# lighting.net
KiCad netlist of a schematic drawn in EAGLE
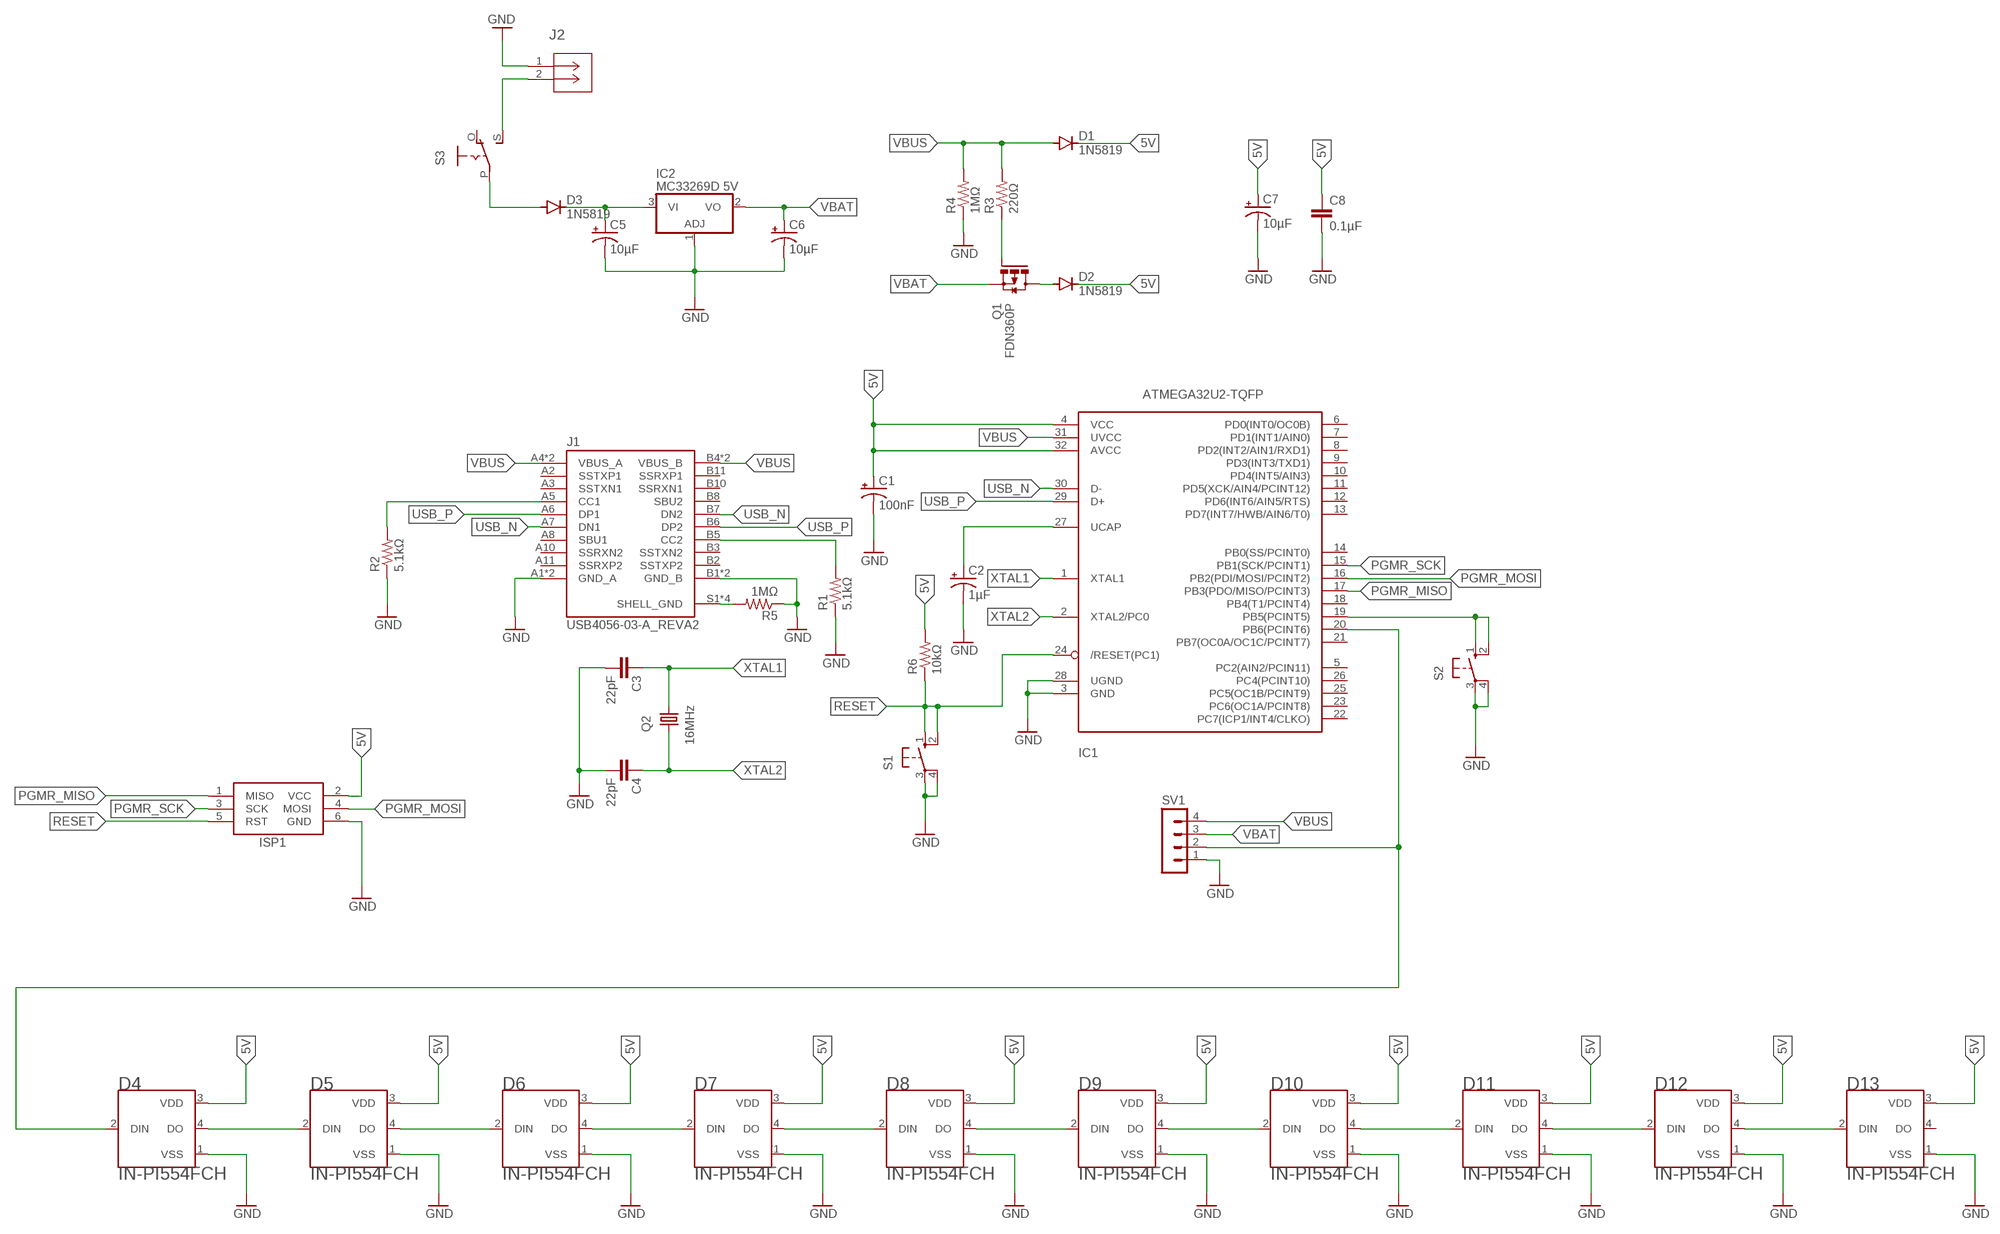
[diagram p0: schematic, sheet 1]

(export (version "E")
  (design (tool "Eeschema 10.0.6"))
  (components
    (comp (ref "C1")
      (value "100nF")
      (footprint "eagle-import:PANASONIC_B")
      (libsource (lib "eagle-import") (part "CPOL-USB"))
    )
    (comp (ref "C2")
      (value "1µF")
      (footprint "eagle-import:E2-5")
      (libsource (lib "eagle-import") (part "CPOL-USE2-5"))
    )
    (comp (ref "C3")
      (value "22pF")
      (footprint "eagle-import:C0402")
      (libsource (lib "eagle-import") (part "C-EUC0402"))
    )
    (comp (ref "C4")
      (value "22pF")
      (footprint "eagle-import:C0402")
      (libsource (lib "eagle-import") (part "C-EUC0402"))
    )
    (comp (ref "C5")
      (value "10µF")
      (footprint "eagle-import:PANASONIC_B")
      (libsource (lib "eagle-import") (part "CPOL-USB"))
    )
    (comp (ref "C6")
      (value "10µF")
      (footprint "eagle-import:PANASONIC_B")
      (libsource (lib "eagle-import") (part "CPOL-USB"))
    )
    (comp (ref "C7")
      (value "10µF")
      (footprint "eagle-import:PANASONIC_B")
      (libsource (lib "eagle-import") (part "CPOL-USB"))
    )
    (comp (ref "C8")
      (value "0.1µF")
      (footprint "eagle-import:C0402")
      (libsource (lib "eagle-import") (part "C-EUC0402"))
    )
    (comp (ref "D1")
      (value "1N5819")
      (footprint "eagle-import:DO15-12")
      (libsource (lib "eagle-import") (part "DIODE-DO15-12"))
    )
    (comp (ref "D2")
      (value "1N5819")
      (footprint "eagle-import:DO15-12")
      (libsource (lib "eagle-import") (part "DIODE-DO15-12"))
    )
    (comp (ref "D3")
      (value "1N5819")
      (footprint "eagle-import:DO15-12")
      (libsource (lib "eagle-import") (part "DIODE-DO15-12"))
    )
    (comp (ref "D4")
      (value "IN-PI554FCH")
      (footprint "eagle-import:LED_IN-PI554FCH")
      (fields (field (name "MANUFACTURER") "Inolux"))
      (libsource (lib "eagle-import") (part "IN-PI554FCH"))
    )
    (comp (ref "D5")
      (value "IN-PI554FCH")
      (footprint "eagle-import:LED_IN-PI554FCH")
      (fields (field (name "MANUFACTURER") "Inolux"))
      (libsource (lib "eagle-import") (part "IN-PI554FCH"))
    )
    (comp (ref "D6")
      (value "IN-PI554FCH")
      (footprint "eagle-import:LED_IN-PI554FCH")
      (fields (field (name "MANUFACTURER") "Inolux"))
      (libsource (lib "eagle-import") (part "IN-PI554FCH"))
    )
    (comp (ref "D7")
      (value "IN-PI554FCH")
      (footprint "eagle-import:LED_IN-PI554FCH")
      (fields (field (name "MANUFACTURER") "Inolux"))
      (libsource (lib "eagle-import") (part "IN-PI554FCH"))
    )
    (comp (ref "D8")
      (value "IN-PI554FCH")
      (footprint "eagle-import:LED_IN-PI554FCH")
      (fields (field (name "MANUFACTURER") "Inolux"))
      (libsource (lib "eagle-import") (part "IN-PI554FCH"))
    )
    (comp (ref "D9")
      (value "IN-PI554FCH")
      (footprint "eagle-import:LED_IN-PI554FCH")
      (fields (field (name "MANUFACTURER") "Inolux"))
      (libsource (lib "eagle-import") (part "IN-PI554FCH"))
    )
    (comp (ref "D10")
      (value "IN-PI554FCH")
      (footprint "eagle-import:LED_IN-PI554FCH")
      (fields (field (name "MANUFACTURER") "Inolux"))
      (libsource (lib "eagle-import") (part "IN-PI554FCH"))
    )
    (comp (ref "D11")
      (value "IN-PI554FCH")
      (footprint "eagle-import:LED_IN-PI554FCH")
      (fields (field (name "MANUFACTURER") "Inolux"))
      (libsource (lib "eagle-import") (part "IN-PI554FCH"))
    )
    (comp (ref "D12")
      (value "IN-PI554FCH")
      (footprint "eagle-import:LED_IN-PI554FCH")
      (fields (field (name "MANUFACTURER") "Inolux"))
      (libsource (lib "eagle-import") (part "IN-PI554FCH"))
    )
    (comp (ref "D13")
      (value "IN-PI554FCH")
      (footprint "eagle-import:LED_IN-PI554FCH")
      (fields (field (name "MANUFACTURER") "Inolux"))
      (libsource (lib "eagle-import") (part "IN-PI554FCH"))
    )
    (comp (ref "IC1")
      (value "ATMEGA32U2-TQFP")
      (footprint "eagle-import:TQFP32-08")
      (libsource (lib "eagle-import") (part "ATMEGA32U2-TQFP"))
    )
    (comp (ref "IC2")
      (value "MC33269D 5V")
      (footprint "eagle-import:DPACK")
      (libsource (lib "eagle-import") (part "MC33269?D"))
    )
    (comp (ref "ISP1")
      (value "AVRISP-BOX")
      (footprint "eagle-import:AVRISP-BOX")
      (libsource (lib "eagle-import") (part "AVRISP-BOX"))
    )
    (comp (ref "J1")
      (value "USB4056-03-A_REVA2")
      (footprint "eagle-import:GCT_USB4056-03-A_REVA2")
      (fields (field (name "MANUFACTURER") "GCT"))
      (libsource (lib "eagle-import") (part "USB4056-03-A_REVA2"))
    )
    (comp (ref "J2")
      (value "BH9VPC 9V")
      (footprint "eagle-import:CONN_BH9VPC_MPD")
      (fields
        (field (name "MANUFACTURER_PART_NUMBER") "BH9VPC")
        (field (name "COPYRIGHT") "Copyright (C) 2024 Ultra Librarian. All rights reserved.")
      )
      (libsource (lib "eagle-import") (part "BH9VPC"))
    )
    (comp (ref "Q1")
      (value "FDN360P")
      (footprint "eagle-import:SUPER-SOT3")
      (libsource (lib "eagle-import") (part "FDN360P"))
    )
    (comp (ref "Q2")
      (value "16MHz")
      (footprint "eagle-import:HC49U-V")
      (libsource (lib "eagle-import") (part "CRYSTALHC49U-V"))
    )
    (comp (ref "R1")
      (value "5.1kΩ")
      (footprint "eagle-import:0207_10")
      (libsource (lib "eagle-import") (part "R-US_0207/10"))
    )
    (comp (ref "R2")
      (value "5.1kΩ")
      (footprint "eagle-import:0207_10")
      (libsource (lib "eagle-import") (part "R-US_0207/10"))
    )
    (comp (ref "R3")
      (value "220Ω")
      (footprint "eagle-import:0207_10")
      (libsource (lib "eagle-import") (part "R-US_0207/10"))
    )
    (comp (ref "R4")
      (value "1MΩ")
      (footprint "eagle-import:0207_10")
      (libsource (lib "eagle-import") (part "R-US_0207/10"))
    )
    (comp (ref "R5")
      (value "1MΩ")
      (footprint "eagle-import:0207_10")
      (libsource (lib "eagle-import") (part "R-US_0207/10"))
    )
    (comp (ref "R6")
      (value "10kΩ")
      (footprint "eagle-import:0207_10")
      (libsource (lib "eagle-import") (part "R-US_0207/10"))
    )
    (comp (ref "S1")
      (value "10-XX")
      (footprint "eagle-import:B3F-10XX")
      (fields (field (name "MPN") "B3F-1000"))
      (libsource (lib "eagle-import") (part "10-XX"))
    )
    (comp (ref "S2")
      (value "10-XX")
      (footprint "eagle-import:B3F-10XX")
      (fields (field (name "MPN") "B3F-1000"))
      (libsource (lib "eagle-import") (part "10-XX"))
    )
    (comp (ref "S3")
      (value "EG1218S")
      (footprint "eagle-import:EG1218")
      (libsource (lib "eagle-import") (part "EG1218S"))
    )
    (comp (ref "SV1")
      (value "MA04-1")
      (footprint "eagle-import:MA04-1")
      (libsource (lib "eagle-import") (part "MA04-1"))
    )
  )
  (nets
    (net (code "1") (name "5V") (class "Default")
      (node (ref "C1") (pin "+") (pinfunction "+_+") (pintype "passive"))
      (node (ref "C7") (pin "+") (pinfunction "+_+") (pintype "passive"))
      (node (ref "C8") (pin "1") (pinfunction "1_1") (pintype "passive"))
      (node (ref "D1") (pin "C") (pinfunction "C_C") (pintype "passive"))
      (node (ref "D10") (pin "3") (pinfunction "VDD_3") (pintype "power_in"))
      (node (ref "D11") (pin "3") (pinfunction "VDD_3") (pintype "power_in"))
      (node (ref "D12") (pin "3") (pinfunction "VDD_3") (pintype "power_in"))
      (node (ref "D13") (pin "3") (pinfunction "VDD_3") (pintype "power_in"))
      (node (ref "D2") (pin "C") (pinfunction "C_C") (pintype "passive"))
      (node (ref "D4") (pin "3") (pinfunction "VDD_3") (pintype "power_in"))
      (node (ref "D5") (pin "3") (pinfunction "VDD_3") (pintype "power_in"))
      (node (ref "D6") (pin "3") (pinfunction "VDD_3") (pintype "power_in"))
      (node (ref "D7") (pin "3") (pinfunction "VDD_3") (pintype "power_in"))
      (node (ref "D8") (pin "3") (pinfunction "VDD_3") (pintype "power_in"))
      (node (ref "D9") (pin "3") (pinfunction "VDD_3") (pintype "power_in"))
      (node (ref "IC1") (pin "32") (pinfunction "AVCC_32") (pintype "bidirectional"))
      (node (ref "IC1") (pin "4") (pinfunction "VCC_4") (pintype "bidirectional"))
      (node (ref "ISP1") (pin "2") (pinfunction "VCC_2") (pintype "power_in"))
      (node (ref "R6") (pin "2") (pinfunction "2_2") (pintype "passive"))
    )
    (net (code "2") (name "GND") (class "Default")
      (node (ref "C1") (pin "-") (pinfunction "-_-") (pintype "passive"))
      (node (ref "C2") (pin "-") (pinfunction "-_-") (pintype "passive"))
      (node (ref "C3") (pin "2") (pinfunction "2_2") (pintype "passive"))
      (node (ref "C4") (pin "2") (pinfunction "2_2") (pintype "passive"))
      (node (ref "C5") (pin "-") (pinfunction "-_-") (pintype "passive"))
      (node (ref "C6") (pin "-") (pinfunction "-_-") (pintype "passive"))
      (node (ref "C7") (pin "-") (pinfunction "-_-") (pintype "passive"))
      (node (ref "C8") (pin "2") (pinfunction "2_2") (pintype "passive"))
      (node (ref "D10") (pin "1") (pinfunction "VSS_1") (pintype "power_in"))
      (node (ref "D11") (pin "1") (pinfunction "VSS_1") (pintype "power_in"))
      (node (ref "D12") (pin "1") (pinfunction "VSS_1") (pintype "power_in"))
      (node (ref "D13") (pin "1") (pinfunction "VSS_1") (pintype "power_in"))
      (node (ref "D4") (pin "1") (pinfunction "VSS_1") (pintype "power_in"))
      (node (ref "D5") (pin "1") (pinfunction "VSS_1") (pintype "power_in"))
      (node (ref "D6") (pin "1") (pinfunction "VSS_1") (pintype "power_in"))
      (node (ref "D7") (pin "1") (pinfunction "VSS_1") (pintype "power_in"))
      (node (ref "D8") (pin "1") (pinfunction "VSS_1") (pintype "power_in"))
      (node (ref "D9") (pin "1") (pinfunction "VSS_1") (pintype "power_in"))
      (node (ref "IC1") (pin "28") (pinfunction "UGND_28") (pintype "bidirectional"))
      (node (ref "IC1") (pin "3") (pinfunction "GND_3") (pintype "bidirectional"))
      (node (ref "IC2") (pin "1") (pinfunction "ADJ_1") (pintype "input"))
      (node (ref "ISP1") (pin "6") (pinfunction "GND_6") (pintype "power_in"))
      (node (ref "J1") (pin "A1") (pinfunction "GND_A_A1") (pintype "power_in"))
      (node (ref "J1") (pin "A12") (pinfunction "GND_A_A12") (pintype "power_in"))
      (node (ref "J1") (pin "B1") (pinfunction "GND_B_B1") (pintype "power_in"))
      (node (ref "J1") (pin "B12") (pinfunction "GND_B_B12") (pintype "power_in"))
      (node (ref "J2") (pin "1") (pinfunction "1_1") (pintype "passive"))
      (node (ref "R1") (pin "1") (pinfunction "1_1") (pintype "passive"))
      (node (ref "R2") (pin "1") (pinfunction "1_1") (pintype "passive"))
      (node (ref "R4") (pin "1") (pinfunction "1_1") (pintype "passive"))
      (node (ref "R5") (pin "1") (pinfunction "1_1") (pintype "passive"))
      (node (ref "S1") (pin "3") (pinfunction "P_3") (pintype "passive"))
      (node (ref "S1") (pin "4") (pinfunction "P1_4") (pintype "passive"))
      (node (ref "S2") (pin "3") (pinfunction "P_3") (pintype "passive"))
      (node (ref "S2") (pin "4") (pinfunction "P1_4") (pintype "passive"))
      (node (ref "SV1") (pin "1") (pinfunction "1_1") (pintype "passive"))
    )
    (net (code "3") (name "Net-(D3-PadA)") (class "Default")
      (node (ref "D3") (pin "A") (pinfunction "A_A") (pintype "passive"))
      (node (ref "S3") (pin "P") (pinfunction "P_P") (pintype "passive"))
    )
    (net (code "4") (name "Net-(D4-DIN)") (class "Default")
      (node (ref "D4") (pin "2") (pinfunction "DIN_2") (pintype "input"))
      (node (ref "IC1") (pin "20") (pinfunction "PB6(PCINT6)_20") (pintype "bidirectional"))
      (node (ref "SV1") (pin "2") (pinfunction "2_2") (pintype "passive"))
    )
    (net (code "5") (name "Net-(D4-DO)") (class "Default")
      (node (ref "D4") (pin "4") (pinfunction "DO_4") (pintype "output"))
      (node (ref "D5") (pin "2") (pinfunction "DIN_2") (pintype "input"))
    )
    (net (code "6") (name "Net-(D5-DO)") (class "Default")
      (node (ref "D5") (pin "4") (pinfunction "DO_4") (pintype "output"))
      (node (ref "D6") (pin "2") (pinfunction "DIN_2") (pintype "input"))
    )
    (net (code "7") (name "Net-(D6-DO)") (class "Default")
      (node (ref "D6") (pin "4") (pinfunction "DO_4") (pintype "output"))
      (node (ref "D7") (pin "2") (pinfunction "DIN_2") (pintype "input"))
    )
    (net (code "8") (name "Net-(D7-DO)") (class "Default")
      (node (ref "D7") (pin "4") (pinfunction "DO_4") (pintype "output"))
      (node (ref "D8") (pin "2") (pinfunction "DIN_2") (pintype "input"))
    )
    (net (code "9") (name "Net-(D8-DO)") (class "Default")
      (node (ref "D8") (pin "4") (pinfunction "DO_4") (pintype "output"))
      (node (ref "D9") (pin "2") (pinfunction "DIN_2") (pintype "input"))
    )
    (net (code "10") (name "Net-(D10-DIN)") (class "Default")
      (node (ref "D10") (pin "2") (pinfunction "DIN_2") (pintype "input"))
      (node (ref "D9") (pin "4") (pinfunction "DO_4") (pintype "output"))
    )
    (net (code "11") (name "Net-(D10-DO)") (class "Default")
      (node (ref "D10") (pin "4") (pinfunction "DO_4") (pintype "output"))
      (node (ref "D11") (pin "2") (pinfunction "DIN_2") (pintype "input"))
    )
    (net (code "12") (name "Net-(D11-DO)") (class "Default")
      (node (ref "D11") (pin "4") (pinfunction "DO_4") (pintype "output"))
      (node (ref "D12") (pin "2") (pinfunction "DIN_2") (pintype "input"))
    )
    (net (code "13") (name "Net-(D12-DO)") (class "Default")
      (node (ref "D12") (pin "4") (pinfunction "DO_4") (pintype "output"))
      (node (ref "D13") (pin "2") (pinfunction "DIN_2") (pintype "input"))
    )
    (net (code "14") (name "Net-(IC1-PB5(PCINT5))") (class "Default")
      (node (ref "IC1") (pin "19") (pinfunction "PB5(PCINT5)_19") (pintype "bidirectional"))
      (node (ref "S2") (pin "1") (pinfunction "S_1") (pintype "passive"))
      (node (ref "S2") (pin "2") (pinfunction "S1_2") (pintype "passive"))
    )
    (net (code "15") (name "Net-(IC1-UCAP)") (class "Default")
      (node (ref "C2") (pin "+") (pinfunction "+_+") (pintype "passive"))
      (node (ref "IC1") (pin "27") (pinfunction "UCAP_27") (pintype "bidirectional"))
    )
    (net (code "16") (name "Net-(IC2-VI)") (class "Default")
      (node (ref "C5") (pin "+") (pinfunction "+_+") (pintype "passive"))
      (node (ref "D3") (pin "C") (pinfunction "C_C") (pintype "passive"))
      (node (ref "IC2") (pin "3") (pinfunction "VI_3") (pintype "input"))
    )
    (net (code "17") (name "Net-(J1-CC1)") (class "Default")
      (node (ref "J1") (pin "A5") (pinfunction "CC1_A5") (pintype "bidirectional"))
      (node (ref "R2") (pin "2") (pinfunction "2_2") (pintype "passive"))
    )
    (net (code "18") (name "Net-(J1-CC2)") (class "Default")
      (node (ref "J1") (pin "B5") (pinfunction "CC2_B5") (pintype "bidirectional"))
      (node (ref "R1") (pin "2") (pinfunction "2_2") (pintype "passive"))
    )
    (net (code "19") (name "Net-(J1-SHELL_GND-PadS1)") (class "Default")
      (node (ref "J1") (pin "S1") (pinfunction "SHELL_GND_S1") (pintype "power_in"))
      (node (ref "J1") (pin "S2") (pinfunction "SHELL_GND_S2") (pintype "power_in"))
      (node (ref "J1") (pin "S3") (pinfunction "SHELL_GND_S3") (pintype "power_in"))
      (node (ref "J1") (pin "S4") (pinfunction "SHELL_GND_S4") (pintype "power_in"))
      (node (ref "R5") (pin "2") (pinfunction "2_2") (pintype "passive"))
    )
    (net (code "20") (name "Net-(J2-Pad2)") (class "Default")
      (node (ref "J2") (pin "2") (pinfunction "2_2") (pintype "passive"))
      (node (ref "S3") (pin "S") (pinfunction "S_S") (pintype "passive"))
    )
    (net (code "21") (name "Net-(Q1-D)") (class "Default")
      (node (ref "D2") (pin "A") (pinfunction "A_A") (pintype "passive"))
      (node (ref "Q1") (pin "3") (pinfunction "D_3") (pintype "passive"))
    )
    (net (code "22") (name "Net-(Q1-G)") (class "Default")
      (node (ref "Q1") (pin "1") (pinfunction "G_1") (pintype "passive"))
      (node (ref "R3") (pin "1") (pinfunction "1_1") (pintype "passive"))
    )
    (net (code "23") (name "PGMR_MISO") (class "Default")
      (node (ref "IC1") (pin "17") (pinfunction "PB3(PDO/MISO/PCINT3)_17") (pintype "bidirectional"))
      (node (ref "ISP1") (pin "1") (pinfunction "MISO_1") (pintype "input"))
    )
    (net (code "24") (name "PGMR_MOSI") (class "Default")
      (node (ref "IC1") (pin "16") (pinfunction "PB2(PDI/MOSI/PCINT2)_16") (pintype "bidirectional"))
      (node (ref "ISP1") (pin "4") (pinfunction "MOSI_4") (pintype "output"))
    )
    (net (code "25") (name "PGMR_SCK") (class "Default")
      (node (ref "IC1") (pin "15") (pinfunction "PB1(SCK/PCINT1)_15") (pintype "bidirectional"))
      (node (ref "ISP1") (pin "3") (pinfunction "SCK_3") (pintype "output"))
    )
    (net (code "26") (name "RESET") (class "Default")
      (node (ref "IC1") (pin "24") (pinfunction "/RESET(PC1)_24") (pintype "bidirectional"))
      (node (ref "ISP1") (pin "5") (pinfunction "RST_5") (pintype "output"))
      (node (ref "R6") (pin "1") (pinfunction "1_1") (pintype "passive"))
      (node (ref "S1") (pin "1") (pinfunction "S_1") (pintype "passive"))
      (node (ref "S1") (pin "2") (pinfunction "S1_2") (pintype "passive"))
    )
    (net (code "27") (name "USB_N") (class "Default")
      (node (ref "IC1") (pin "30") (pinfunction "D-_30") (pintype "bidirectional"))
      (node (ref "J1") (pin "A7") (pinfunction "DN1_A7") (pintype "bidirectional"))
      (node (ref "J1") (pin "B7") (pinfunction "DN2_B7") (pintype "bidirectional"))
    )
    (net (code "28") (name "USB_P") (class "Default")
      (node (ref "IC1") (pin "29") (pinfunction "D+_29") (pintype "bidirectional"))
      (node (ref "J1") (pin "A6") (pinfunction "DP1_A6") (pintype "bidirectional"))
      (node (ref "J1") (pin "B6") (pinfunction "DP2_B6") (pintype "bidirectional"))
    )
    (net (code "29") (name "VBAT") (class "Default")
      (node (ref "C6") (pin "+") (pinfunction "+_+") (pintype "passive"))
      (node (ref "IC2") (pin "2") (pinfunction "VO_2") (pintype "passive"))
      (node (ref "Q1") (pin "2") (pinfunction "S_2") (pintype "passive"))
      (node (ref "SV1") (pin "3") (pinfunction "3_3") (pintype "passive"))
    )
    (net (code "30") (name "VBUS") (class "Default")
      (node (ref "D1") (pin "A") (pinfunction "A_A") (pintype "passive"))
      (node (ref "IC1") (pin "31") (pinfunction "UVCC_31") (pintype "bidirectional"))
      (node (ref "J1") (pin "A4") (pinfunction "VBUS_A_A4") (pintype "power_in"))
      (node (ref "J1") (pin "A9") (pinfunction "VBUS_A_A9") (pintype "power_in"))
      (node (ref "J1") (pin "B4") (pinfunction "VBUS_B_B4") (pintype "power_in"))
      (node (ref "J1") (pin "B9") (pinfunction "VBUS_B_B9") (pintype "power_in"))
      (node (ref "R3") (pin "2") (pinfunction "2_2") (pintype "passive"))
      (node (ref "R4") (pin "2") (pinfunction "2_2") (pintype "passive"))
      (node (ref "SV1") (pin "4") (pinfunction "4_4") (pintype "passive"))
    )
    (net (code "31") (name "XTAL1") (class "Default")
      (node (ref "C3") (pin "1") (pinfunction "1_1") (pintype "passive"))
      (node (ref "IC1") (pin "1") (pinfunction "XTAL1_1") (pintype "bidirectional"))
      (node (ref "Q2") (pin "2") (pinfunction "2_2") (pintype "passive"))
    )
    (net (code "32") (name "XTAL2") (class "Default")
      (node (ref "C4") (pin "1") (pinfunction "1_1") (pintype "passive"))
      (node (ref "IC1") (pin "2") (pinfunction "XTAL2/PC0_2") (pintype "bidirectional"))
      (node (ref "Q2") (pin "1") (pinfunction "1_1") (pintype "passive"))
    )
    (net (code "33") (name "unconnected-(D13-DO-Pad4)") (class "Default")
      (node (ref "D13") (pin "4") (pinfunction "DO_4") (pintype "output"))
    )
    (net (code "34") (name "unconnected-(IC1-PB0(SS{slash}PCINT0)-Pad14)") (class "Default")
      (node (ref "IC1") (pin "14") (pinfunction "PB0(SS/PCINT0)_14") (pintype "bidirectional"))
    )
    (net (code "35") (name "unconnected-(IC1-PB4(T1{slash}PCINT4)-Pad18)") (class "Default")
      (node (ref "IC1") (pin "18") (pinfunction "PB4(T1/PCINT4)_18") (pintype "bidirectional"))
    )
    (net (code "36") (name "unconnected-(IC1-PB7(OC0A{slash}OC1C{slash}PCINT7)-Pad21)") (class "Default")
      (node (ref "IC1") (pin "21") (pinfunction "PB7(OC0A/OC1C/PCINT7)_21") (pintype "bidirectional"))
    )
    (net (code "37") (name "unconnected-(IC1-PC2(AIN2{slash}PCIN11)-Pad5)") (class "Default")
      (node (ref "IC1") (pin "5") (pinfunction "PC2(AIN2/PCIN11)_5") (pintype "bidirectional"))
    )
    (net (code "38") (name "unconnected-(IC1-PC4(PCINT10)-Pad26)") (class "Default")
      (node (ref "IC1") (pin "26") (pinfunction "PC4(PCINT10)_26") (pintype "bidirectional"))
    )
    (net (code "39") (name "unconnected-(IC1-PC5(OC1B{slash}PCINT9)-Pad25)") (class "Default")
      (node (ref "IC1") (pin "25") (pinfunction "PC5(OC1B/PCINT9)_25") (pintype "bidirectional"))
    )
    (net (code "40") (name "unconnected-(IC1-PC6(OC1A{slash}PCINT8)-Pad23)") (class "Default")
      (node (ref "IC1") (pin "23") (pinfunction "PC6(OC1A/PCINT8)_23") (pintype "bidirectional"))
    )
    (net (code "41") (name "unconnected-(IC1-PC7(ICP1{slash}INT4{slash}CLKO)-Pad22)") (class "Default")
      (node (ref "IC1") (pin "22") (pinfunction "PC7(ICP1/INT4/CLKO)_22") (pintype "bidirectional"))
    )
    (net (code "42") (name "unconnected-(IC1-PD0(INT0{slash}OC0B)-Pad6)") (class "Default")
      (node (ref "IC1") (pin "6") (pinfunction "PD0(INT0/OC0B)_6") (pintype "bidirectional"))
    )
    (net (code "43") (name "unconnected-(IC1-PD1(INT1{slash}AIN0)-Pad7)") (class "Default")
      (node (ref "IC1") (pin "7") (pinfunction "PD1(INT1/AIN0)_7") (pintype "bidirectional"))
    )
    (net (code "44") (name "unconnected-(IC1-PD2(INT2{slash}AIN1{slash}RXD1)-Pad8)") (class "Default")
      (node (ref "IC1") (pin "8") (pinfunction "PD2(INT2/AIN1/RXD1)_8") (pintype "bidirectional"))
    )
    (net (code "45") (name "unconnected-(IC1-PD3(INT3{slash}TXD1)-Pad9)") (class "Default")
      (node (ref "IC1") (pin "9") (pinfunction "PD3(INT3/TXD1)_9") (pintype "bidirectional"))
    )
    (net (code "46") (name "unconnected-(IC1-PD4(INT5{slash}AIN3)-Pad10)") (class "Default")
      (node (ref "IC1") (pin "10") (pinfunction "PD4(INT5/AIN3)_10") (pintype "bidirectional"))
    )
    (net (code "47") (name "unconnected-(IC1-PD5(XCK{slash}AIN4{slash}PCINT12)-Pad11)") (class "Default")
      (node (ref "IC1") (pin "11") (pinfunction "PD5(XCK/AIN4/PCINT12)_11") (pintype "bidirectional"))
    )
    (net (code "48") (name "unconnected-(IC1-PD6(INT6{slash}AIN5{slash}RTS)-Pad12)") (class "Default")
      (node (ref "IC1") (pin "12") (pinfunction "PD6(INT6/AIN5/RTS)_12") (pintype "bidirectional"))
    )
    (net (code "49") (name "unconnected-(IC1-PD7(INT7{slash}HWB{slash}AIN6{slash}T0)-Pad13)") (class "Default")
      (node (ref "IC1") (pin "13") (pinfunction "PD7(INT7/HWB/AIN6/T0)_13") (pintype "bidirectional"))
    )
    (net (code "50") (name "unconnected-(J1-SBU1-PadA8)") (class "Default")
      (node (ref "J1") (pin "A8") (pinfunction "SBU1_A8") (pintype "bidirectional"))
    )
    (net (code "51") (name "unconnected-(J1-SBU2-PadB8)") (class "Default")
      (node (ref "J1") (pin "B8") (pinfunction "SBU2_B8") (pintype "bidirectional"))
    )
    (net (code "52") (name "unconnected-(J1-SSRXN1-PadB10)") (class "Default")
      (node (ref "J1") (pin "B10") (pinfunction "SSRXN1_B10") (pintype "bidirectional"))
    )
    (net (code "53") (name "unconnected-(J1-SSRXN2-PadA10)") (class "Default")
      (node (ref "J1") (pin "A10") (pinfunction "SSRXN2_A10") (pintype "bidirectional"))
    )
    (net (code "54") (name "unconnected-(J1-SSRXP1-PadB11)") (class "Default")
      (node (ref "J1") (pin "B11") (pinfunction "SSRXP1_B11") (pintype "bidirectional"))
    )
    (net (code "55") (name "unconnected-(J1-SSRXP2-PadA11)") (class "Default")
      (node (ref "J1") (pin "A11") (pinfunction "SSRXP2_A11") (pintype "bidirectional"))
    )
    (net (code "56") (name "unconnected-(J1-SSTXN1-PadA3)") (class "Default")
      (node (ref "J1") (pin "A3") (pinfunction "SSTXN1_A3") (pintype "bidirectional"))
    )
    (net (code "57") (name "unconnected-(J1-SSTXN2-PadB3)") (class "Default")
      (node (ref "J1") (pin "B3") (pinfunction "SSTXN2_B3") (pintype "bidirectional"))
    )
    (net (code "58") (name "unconnected-(J1-SSTXP1-PadA2)") (class "Default")
      (node (ref "J1") (pin "A2") (pinfunction "SSTXP1_A2") (pintype "bidirectional"))
    )
    (net (code "59") (name "unconnected-(J1-SSTXP2-PadB2)") (class "Default")
      (node (ref "J1") (pin "B2") (pinfunction "SSTXP2_B2") (pintype "bidirectional"))
    )
    (net (code "60") (name "unconnected-(S3-PadO)") (class "Default")
      (node (ref "S3") (pin "O") (pinfunction "O_O") (pintype "passive"))
    )
  )
)
